# GSM-LCD-ATmega32.net
KiCad netlist of a schematic drawn in Altium Designer
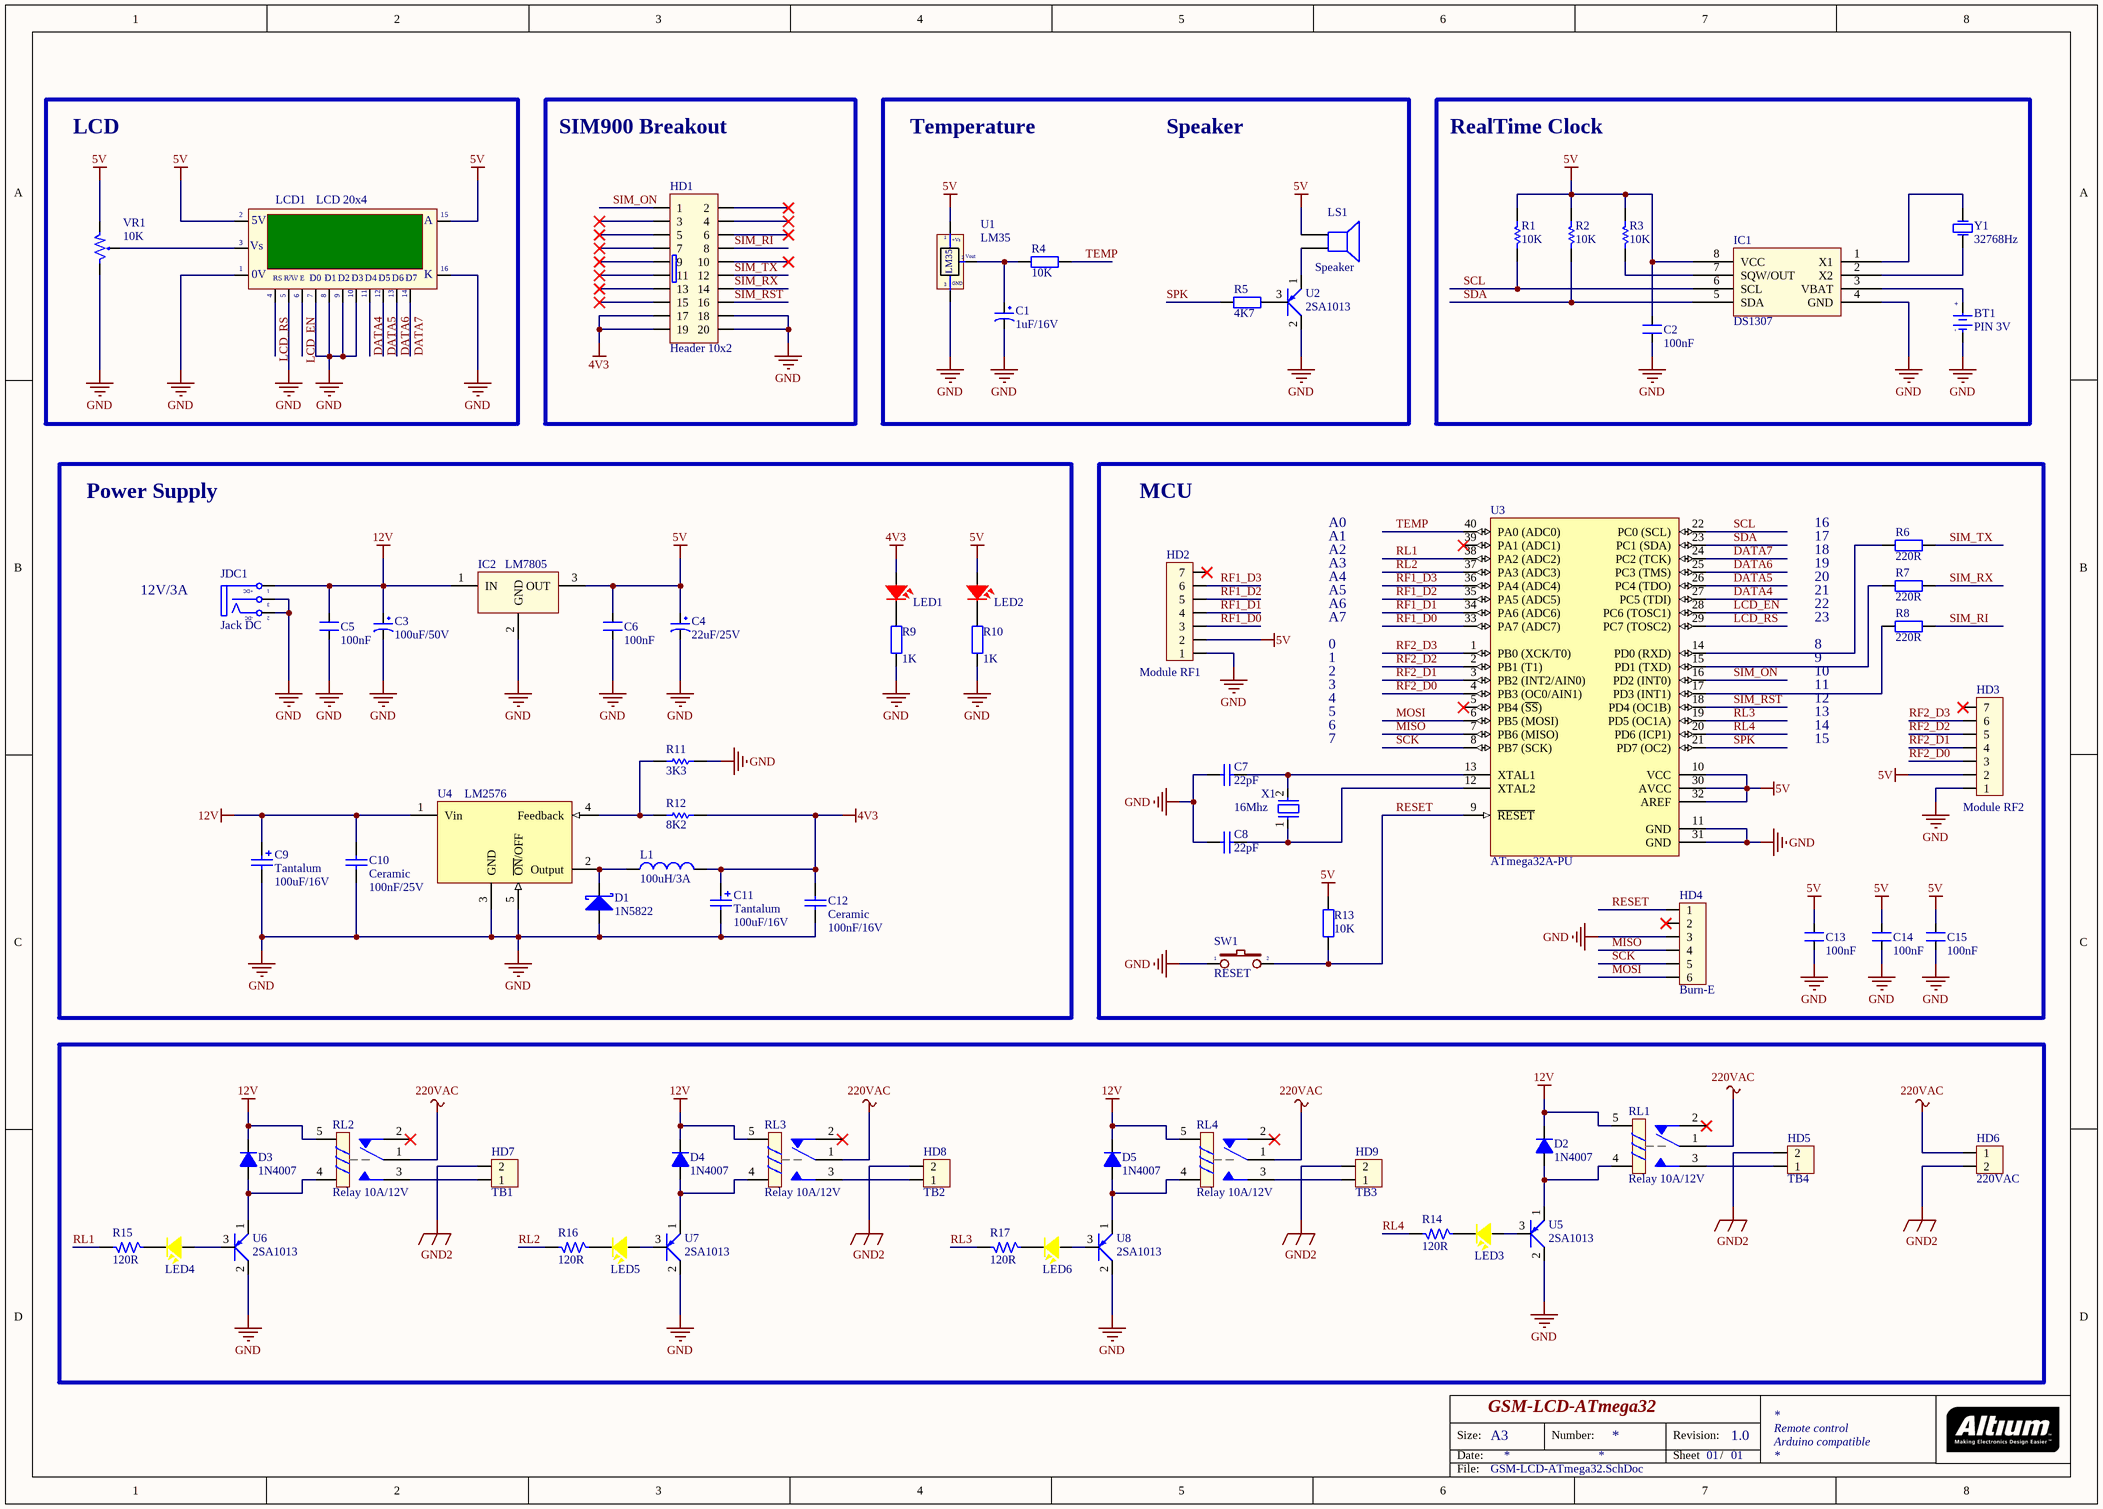
[diagram p0: GSM-LCD-ATmega32.SchDoc]

(export (version "E")
  (design (tool "Eeschema 10.0.6"))
  (components
    (comp (ref "BT1")
      (value "PIN 3V")
      (footprint "PIN3V")
      (description "Battery 3VDC")
      (libsource (lib "lpson") (part "PIN 3V"))
    )
    (comp (ref "C1")
      (value "1uF/16V")
      (footprint "CAP_1UF_50V")
      (description "Cap 100uF/35V - 470uF/16V")
      (libsource (lib "VNELEK") (part "CP3"))
    )
    (comp (ref "C2")
      (value "100nF")
      (footprint "Tu gom 104")
      (description "Cap np 104 => 105pF")
      (libsource (lib "VNELEK") (part "CN2"))
    )
    (comp (ref "C3")
      (value "100uF/50V")
      (footprint "CAP_100UF_50V")
      (description "Cap 100uF/35V - 470uF/16V")
      (libsource (lib "VNELEK") (part "CP3"))
    )
    (comp (ref "C4")
      (value "22uF/25V")
      (footprint "CAP_22UF_50V")
      (description "Cap 100uF/35V - 470uF/16V")
      (libsource (lib "VNELEK") (part "CP3"))
    )
    (comp (ref "C5")
      (value "100nF")
      (footprint "Tu gom 104")
      (description "Cap np 104 => 105pF")
      (libsource (lib "VNELEK") (part "CN2"))
    )
    (comp (ref "C6")
      (value "100nF")
      (footprint "Tu gom 104")
      (description "Cap np 104 => 105pF")
      (libsource (lib "VNELEK") (part "CN2"))
    )
    (comp (ref "C7")
      (value "22pF")
      (footprint "Tu 33p")
      (description "CAP NPO CAPNTO 1nF 100V 10%")
      (fields (field (name "Comment") "5AK102KABAA"))
      (libsource (lib "lpson") (part "5AK102KABAA"))
    )
    (comp (ref "C8")
      (value "22pF")
      (footprint "Tu 33p")
      (description "CAP NPO CAPNTO 1nF 100V 10%")
      (fields (field (name "Comment") "5AK102KABAA"))
      (libsource (lib "lpson") (part "5AK102KABAA"))
    )
    (comp (ref "C9")
      (value "Tantalum")
      (footprint "CAP_100UF_16V")
      (description "Tantalum Capacitor")
      (fields (field (name "ALTIUM_VALUE") "100uF/16V"))
      (libsource (lib "PassiveComponents_Sau") (part "Cap Pol2"))
    )
    (comp (ref "C10")
      (value "Ceramic")
      (footprint "Tu gom 104")
      (description "CeramicCapacitor, 16V, 2.54mm")
      (fields (field (name "ALTIUM_VALUE") "100nF/25V"))
      (libsource (lib "PassiveComponents_Sau") (part "Cap Cera"))
    )
    (comp (ref "C11")
      (value "Tantalum")
      (footprint "CAP_100UF_16V")
      (description "Tantalum Capacitor")
      (fields (field (name "ALTIUM_VALUE") "100uF/16V"))
      (libsource (lib "PassiveComponents_Sau") (part "Cap Pol2"))
    )
    (comp (ref "C12")
      (value "Ceramic")
      (footprint "Tu gom 104")
      (description "CeramicCapacitor, 16V, 2.54mm")
      (fields (field (name "ALTIUM_VALUE") "100nF/16V"))
      (libsource (lib "PassiveComponents_Sau") (part "Cap Cera"))
    )
    (comp (ref "C13")
      (value "100nF")
      (footprint "Tu gom 104")
      (description "Cap np 104 => 105pF")
      (libsource (lib "VNELEK") (part "CN2"))
    )
    (comp (ref "C14")
      (value "100nF")
      (footprint "Tu gom 104")
      (description "Cap np 104 => 105pF")
      (libsource (lib "VNELEK") (part "CN2"))
    )
    (comp (ref "C15")
      (value "100nF")
      (footprint "Tu gom 104")
      (description "Cap np 104 => 105pF")
      (libsource (lib "VNELEK") (part "CN2"))
    )
    (comp (ref "D1")
      (value "1N5822")
      (footprint "1N5822")
      (description "Schottky Rectifier, 40V-3A")
      (fields (field (name "PUBLISHER") "Altium Limited"))
      (libsource (lib "Diodes_Sau") (part "1N5822"))
    )
    (comp (ref "D2")
      (value "1N4007")
      (footprint "1N4007")
      (description "Diode 1A")
      (libsource (lib "VNELEK") (part "D1A"))
    )
    (comp (ref "D3")
      (value "1N4007")
      (footprint "1N4007")
      (description "Diode 1A")
      (libsource (lib "VNELEK") (part "D1A"))
    )
    (comp (ref "D4")
      (value "1N4007")
      (footprint "1N4007")
      (description "Diode 1A")
      (libsource (lib "VNELEK") (part "D1A"))
    )
    (comp (ref "D5")
      (value "1N4007")
      (footprint "1N4007")
      (description "Diode 1A")
      (libsource (lib "VNELEK") (part "D1A"))
    )
    (comp (ref "HD1")
      (value "Header 10x2")
      (footprint "Female Header_10x2")
      (libsource (lib "Tran Tuan") (part "HED10X2"))
    )
    (comp (ref "HD2")
      (value "Module RF1")
      (footprint "FM-Header 7")
      (description "Header 7")
      (libsource (lib "") (part "Hed7_1"))
    )
    (comp (ref "HD3")
      (value "Module RF2")
      (footprint "FM-Header 7")
      (description "Header 7")
      (libsource (lib "Tran Tuan") (part "Hed7"))
    )
    (comp (ref "HD4")
      (value "Burn-E")
      (footprint "CON6")
      (description "Header 6 (Trang)")
      (libsource (lib "Tran Tuan") (part "Hed6"))
    )
    (comp (ref "HD5")
      (value "TB4")
      (footprint "DOMINO 2_pitch 8.5mm")
      (description "Domino 2")
      (libsource (lib "VNELEK") (part "Hed2"))
    )
    (comp (ref "HD6")
      (value "220VAC")
      (footprint "DOMINO 2_pitch 8.5mm")
      (description "Domino 2")
      (libsource (lib "") (part "Hed2_1"))
    )
    (comp (ref "HD7")
      (value "TB1")
      (footprint "DOMINO 2_pitch 8.5mm")
      (description "Domino 2")
      (libsource (lib "VNELEK") (part "Hed2"))
    )
    (comp (ref "HD8")
      (value "TB2")
      (footprint "DOMINO 2_pitch 8.5mm")
      (description "Domino 2")
      (libsource (lib "VNELEK") (part "Hed2"))
    )
    (comp (ref "HD9")
      (value "TB3")
      (footprint "DOMINO 2_pitch 8.5mm")
      (description "Domino 2")
      (libsource (lib "VNELEK") (part "Hed2"))
    )
    (comp (ref "IC1")
      (value "DS1307")
      (footprint "DS1307")
      (description "Serial, I2C Real-Time Clock")
      (libsource (lib "Tran Tuan") (part "DS1307"))
    )
    (comp (ref "IC2")
      (value "LM7805")
      (footprint "LM7805_TN_S")
      (description "On ap +, from + 5 to + 24VDC")
      (libsource (lib "VNELEK") (part "LM78xx"))
    )
    (comp (ref "JDC1")
      (value "Jack DC")
      (footprint "JACK DC-IN")
      (description "Jac DC input")
      (libsource (lib "VNELEK") (part "DCIN"))
    )
    (comp (ref "L1")
      (value "100uH/3A")
      (footprint "Inductor 150mH")
      (description "Inductor")
      (fields (field (name "Comment") "LD26W8-151N") (field (name "PUBLISHER") "Altium Limited"))
      (libsource (lib "PassiveComponents_Sau") (part "Inductor"))
    )
    (comp (ref "LCD1")
      (value "LCD 20x4")
      (footprint "LCD20x4")
      (description "LCD dipslay 20 char, 4 line")
      (libsource (lib "VNELEK") (part "LCD16x2A"))
    )
    (comp (ref "LED1")
      (value "LED-RED")
      (footprint "LED3R")
      (description "LED Single")
      (libsource (lib "Tran Tuan") (part "LED-RED"))
    )
    (comp (ref "LED2")
      (value "LED-RED")
      (footprint "LED3R")
      (description "LED Single")
      (libsource (lib "Tran Tuan") (part "LED-RED"))
    )
    (comp (ref "LED3")
      (value "LED-YELLOW")
      (footprint "LED3Y")
      (description "LED Single")
      (libsource (lib "Tran Tuan") (part "LED-YELLOW"))
    )
    (comp (ref "LED4")
      (value "LED-YELLOW")
      (footprint "LED3Y")
      (description "LED Single")
      (libsource (lib "Tran Tuan") (part "LED-YELLOW"))
    )
    (comp (ref "LED5")
      (value "LED-YELLOW")
      (footprint "LED3Y")
      (description "LED Single")
      (libsource (lib "Tran Tuan") (part "LED-YELLOW"))
    )
    (comp (ref "LED6")
      (value "LED-YELLOW")
      (footprint "LED3Y")
      (description "LED Single")
      (libsource (lib "Tran Tuan") (part "LED-YELLOW"))
    )
    (comp (ref "LS1")
      (value "Speaker")
      (footprint "SPEAKER")
      (description "Loudspeaker")
      (fields (field (name "PUBLISHER") "Altium Limited"))
      (libsource (lib "Miscellaneous Devices") (part "Speaker"))
    )
    (comp (ref "R1")
      (value "10K")
      (footprint "RES 1/4W CFR25")
      (libsource (lib "lpson") (part "CF1/4W1KJ25"))
    )
    (comp (ref "R2")
      (value "10K")
      (footprint "RES 1/4W CFR25")
      (libsource (lib "lpson") (part "CF1/4W1KJ25"))
    )
    (comp (ref "R3")
      (value "10K")
      (footprint "RES 1/4W CFR25")
      (libsource (lib "lpson") (part "CF1/4W1KJ25"))
    )
    (comp (ref "R4")
      (value "10K")
      (footprint "RES 1/4W CFR25")
      (description "Resistor")
      (fields (field (name "Comment") "Res2") (field (name "PUBLISHER") "Altium Limited"))
      (libsource (lib "Miscellaneous Devices") (part "Res2"))
    )
    (comp (ref "R5")
      (value "4K7")
      (footprint "RES 1/4W CFR25")
      (description "Resistor")
      (fields (field (name "Comment") "Res2") (field (name "PUBLISHER") "Altium Limited"))
      (libsource (lib "Miscellaneous Devices") (part "Res2"))
    )
    (comp (ref "R6")
      (value "220R")
      (footprint "RES 1/4W CFR25")
      (description "Resistor")
      (fields (field (name "Comment") "Res2") (field (name "PUBLISHER") "Altium Limited"))
      (libsource (lib "Miscellaneous Devices") (part "Res2"))
    )
    (comp (ref "R7")
      (value "220R")
      (footprint "RES 1/4W CFR25")
      (description "Resistor")
      (fields (field (name "Comment") "Res2") (field (name "PUBLISHER") "Altium Limited"))
      (libsource (lib "Miscellaneous Devices") (part "Res2"))
    )
    (comp (ref "R8")
      (value "220R")
      (footprint "RES 1/4W CFR25")
      (description "Resistor")
      (fields (field (name "Comment") "Res2") (field (name "PUBLISHER") "Altium Limited"))
      (libsource (lib "Miscellaneous Devices") (part "Res2"))
    )
    (comp (ref "R9")
      (value "1K")
      (footprint "RES 1/4W CFR25")
      (description "Resistor")
      (fields (field (name "Comment") "Res2") (field (name "PUBLISHER") "Altium Limited"))
      (libsource (lib "") (part "Res2_1"))
    )
    (comp (ref "R10")
      (value "1K")
      (footprint "RES 1/4W CFR25")
      (description "Resistor")
      (fields (field (name "Comment") "Res2") (field (name "PUBLISHER") "Altium Limited"))
      (libsource (lib "") (part "Res2_1"))
    )
    (comp (ref "R11")
      (value "3K3")
      (footprint "RES 1/4W CFR25")
      (description "Resistor 1/4W, AXIAL-0.3")
      (fields (field (name "Comment") "CFR25S"))
      (libsource (lib "Resistors_Sau") (part "Res1"))
    )
    (comp (ref "R12")
      (value "8K2")
      (footprint "RES 1/4W CFR25")
      (description "Resistor 1/4W, AXIAL-0.3")
      (fields (field (name "Comment") "CFR25S"))
      (libsource (lib "Resistors_Sau") (part "Res1"))
    )
    (comp (ref "R13")
      (value "10K")
      (footprint "RES 1/4W CFR25")
      (description "Resistor")
      (fields (field (name "Comment") "Res2") (field (name "PUBLISHER") "Altium Limited"))
      (libsource (lib "") (part "Res2_1"))
    )
    (comp (ref "R14")
      (value "120R")
      (footprint "RES 1/4W CFR25")
      (description "Resistor 1/4W")
      (libsource (lib "VNELEK") (part "R"))
    )
    (comp (ref "R15")
      (value "120R")
      (footprint "RES 1/4W CFR25")
      (description "Resistor 1/4W")
      (libsource (lib "VNELEK") (part "R"))
    )
    (comp (ref "R16")
      (value "120R")
      (footprint "RES 1/4W CFR25")
      (description "Resistor 1/4W")
      (libsource (lib "VNELEK") (part "R"))
    )
    (comp (ref "R17")
      (value "120R")
      (footprint "RES 1/4W CFR25")
      (description "Resistor 1/4W")
      (libsource (lib "VNELEK") (part "R"))
    )
    (comp (ref "RL1")
      (value "Relay 10A/12V")
      (footprint "RL_10A_12V")
      (description "Relay SPDT,10A - 12VDC 5 Pin")
      (libsource (lib "VNELEK") (part "Relay 1"))
    )
    (comp (ref "RL2")
      (value "Relay 10A/12V")
      (footprint "RL_10A_12V")
      (description "Relay SPDT,10A - 12VDC 5 Pin")
      (libsource (lib "VNELEK") (part "Relay 1"))
    )
    (comp (ref "RL3")
      (value "Relay 10A/12V")
      (footprint "RL_10A_12V")
      (description "Relay SPDT,10A - 12VDC 5 Pin")
      (libsource (lib "VNELEK") (part "Relay 1"))
    )
    (comp (ref "RL4")
      (value "Relay 10A/12V")
      (footprint "RL_10A_12V")
      (description "Relay SPDT,10A - 12VDC 5 Pin")
      (libsource (lib "VNELEK") (part "Relay 1"))
    )
    (comp (ref "SW1")
      (value "RESET")
      (footprint "BUTTON 2PIN TRON")
      (description "Switch button 2 pin")
      (libsource (lib "VNELEK") (part "SW2"))
    )
    (comp (ref "U1")
      (value "LM35")
      (footprint "LM35")
      (description "Teminal")
      (libsource (lib "VNELEK") (part "LM35"))
    )
    (comp (ref "U2")
      (value "2SA1013")
      (footprint "2SA1013")
      (description "PNP Epitaxial Silicon Transistor")
      (libsource (lib "Tran Tuan") (part "2SA1013"))
    )
    (comp (ref "U3")
      (value "ATmega32A-PU")
      (footprint "ATmega32A")
      (fields (field (name "PUBLISHER") "Altium Limited"))
      (libsource (lib "Atmel Microcontroller 8-Bit megaAVR") (part "ATmega32A-PU"))
    )
    (comp (ref "U4")
      (value "LM2576")
      (footprint "LM2576_DIP")
      (description "3.0 A, 15 V, Step-Down  Switching Regulator")
      (libsource (lib "AnalogICs_Sau") (part "LM2576"))
    )
    (comp (ref "U5")
      (value "2SA1013")
      (footprint "2SA1013")
      (description "PNP Epitaxial Silicon Transistor")
      (libsource (lib "Tran Tuan") (part "2SA1013"))
    )
    (comp (ref "U6")
      (value "2SA1013")
      (footprint "2SA1013")
      (description "PNP Epitaxial Silicon Transistor")
      (libsource (lib "Tran Tuan") (part "2SA1013"))
    )
    (comp (ref "U7")
      (value "2SA1013")
      (footprint "2SA1013")
      (description "PNP Epitaxial Silicon Transistor")
      (libsource (lib "Tran Tuan") (part "2SA1013"))
    )
    (comp (ref "U8")
      (value "2SA1013")
      (footprint "2SA1013")
      (description "PNP Epitaxial Silicon Transistor")
      (libsource (lib "Tran Tuan") (part "2SA1013"))
    )
    (comp (ref "VR1")
      (value "10K")
      (footprint "VR1")
      (description "Var Resistor")
      (libsource (lib "VNELEK") (part "VR1"))
    )
    (comp (ref "X1")
      (value "16Mhz")
      (footprint "CRYSTAL 16Mhz")
      (description "Crystal For all Crystal 2pin.")
      (libsource (lib "lpson") (part "XT2"))
    )
    (comp (ref "Y1")
      (value "32768Hz")
      (footprint "Crystal 32.768 Khz_stand")
      (description "Crystal Oscillator 30ppm 20.000MHz")
      (fields (field (name "Comment") "HC49S-20-C-30-30-F-20.000MHz"))
      (libsource (lib "lpson") (part "HC49S-20-C-30-30-F-20.000MHz"))
    )
  )
  (nets
    (net (code "1") (name "/DATA4") (class "Default")
      (node (ref "LCD1") (pin "11") (pinfunction "D4_11") (pintype "passive"))
      (node (ref "U3") (pin "27") (pinfunction "PC5_(TDI)_27") (pintype "bidirectional"))
    )
    (net (code "2") (name "/DATA5") (class "Default")
      (node (ref "LCD1") (pin "12") (pinfunction "D5_12") (pintype "passive"))
      (node (ref "U3") (pin "26") (pinfunction "PC4_(TDO)_26") (pintype "bidirectional"))
    )
    (net (code "3") (name "/DATA6") (class "Default")
      (node (ref "LCD1") (pin "13") (pinfunction "D6_13") (pintype "passive"))
      (node (ref "U3") (pin "25") (pinfunction "PC3_(TMS)_25") (pintype "bidirectional"))
    )
    (net (code "4") (name "/DATA7") (class "Default")
      (node (ref "LCD1") (pin "14") (pinfunction "D7_14") (pintype "passive"))
      (node (ref "U3") (pin "24") (pinfunction "PC2_(TCK)_24") (pintype "bidirectional"))
    )
    (net (code "5") (name "/LCD_EN") (class "Default")
      (node (ref "LCD1") (pin "6") (pinfunction "~{EN}_6") (pintype "passive"))
      (node (ref "U3") (pin "28") (pinfunction "PC6_(TOSC1)_28") (pintype "bidirectional"))
    )
    (net (code "6") (name "/LCD_RS") (class "Default")
      (node (ref "LCD1") (pin "4") (pinfunction "RS_4") (pintype "passive"))
      (node (ref "U3") (pin "29") (pinfunction "PC7_(TOSC2)_29") (pintype "bidirectional"))
    )
    (net (code "7") (name "/MISO") (class "Default")
      (node (ref "HD4") (pin "4") (pinfunction "4_4") (pintype "passive"))
      (node (ref "U3") (pin "7") (pinfunction "PB6_(MISO)_7") (pintype "bidirectional"))
    )
    (net (code "8") (name "/MOSI") (class "Default")
      (node (ref "HD4") (pin "6") (pinfunction "6_6") (pintype "passive"))
      (node (ref "U3") (pin "6") (pinfunction "PB5_(MOSI)_6") (pintype "bidirectional"))
    )
    (net (code "9") (name "/RESET") (class "Default")
      (node (ref "HD4") (pin "1") (pinfunction "1_1") (pintype "passive"))
      (node (ref "R13") (pin "1") (pinfunction "1_1") (pintype "passive"))
      (node (ref "SW1") (pin "2") (pinfunction "2_2") (pintype "passive"))
      (node (ref "U3") (pin "9") (pinfunction "~{RESET}_9") (pintype "input"))
    )
    (net (code "10") (name "/RF1_D0") (class "Default")
      (node (ref "HD2") (pin "3") (pinfunction "3_3") (pintype "passive"))
      (node (ref "U3") (pin "33") (pinfunction "PA7_(ADC7)_33") (pintype "bidirectional"))
    )
    (net (code "11") (name "/RF1_D1") (class "Default")
      (node (ref "HD2") (pin "4") (pinfunction "4_4") (pintype "passive"))
      (node (ref "U3") (pin "34") (pinfunction "PA6_(ADC6)_34") (pintype "bidirectional"))
    )
    (net (code "12") (name "/RF1_D2") (class "Default")
      (node (ref "HD2") (pin "5") (pinfunction "5_5") (pintype "passive"))
      (node (ref "U3") (pin "35") (pinfunction "PA5_(ADC5)_35") (pintype "bidirectional"))
    )
    (net (code "13") (name "/RF1_D3") (class "Default")
      (node (ref "HD2") (pin "6") (pinfunction "6_6") (pintype "passive"))
      (node (ref "U3") (pin "36") (pinfunction "PA4_(ADC4)_36") (pintype "bidirectional"))
    )
    (net (code "14") (name "/RF2_D0") (class "Default")
      (node (ref "HD3") (pin "3") (pinfunction "3_3") (pintype "passive"))
      (node (ref "U3") (pin "4") (pinfunction "PB3_(OC0/AIN1)_4") (pintype "bidirectional"))
    )
    (net (code "15") (name "/RF2_D1") (class "Default")
      (node (ref "HD3") (pin "4") (pinfunction "4_4") (pintype "passive"))
      (node (ref "U3") (pin "3") (pinfunction "PB2_(INT2/AIN0)_3") (pintype "bidirectional"))
    )
    (net (code "16") (name "/RF2_D2") (class "Default")
      (node (ref "HD3") (pin "5") (pinfunction "5_5") (pintype "passive"))
      (node (ref "U3") (pin "2") (pinfunction "PB1_(T1)_2") (pintype "bidirectional"))
    )
    (net (code "17") (name "/RF2_D3") (class "Default")
      (node (ref "HD3") (pin "6") (pinfunction "6_6") (pintype "passive"))
      (node (ref "U3") (pin "1") (pinfunction "PB0_(XCK/T0)_1") (pintype "bidirectional"))
    )
    (net (code "18") (name "/RL1") (class "Default")
      (node (ref "R15") (pin "2") (pinfunction "2_2") (pintype "passive"))
      (node (ref "U3") (pin "38") (pinfunction "PA2_(ADC2)_38") (pintype "bidirectional"))
    )
    (net (code "19") (name "/RL2") (class "Default")
      (node (ref "R16") (pin "2") (pinfunction "2_2") (pintype "passive"))
      (node (ref "U3") (pin "37") (pinfunction "PA3_(ADC3)_37") (pintype "bidirectional"))
    )
    (net (code "20") (name "/RL3") (class "Default")
      (node (ref "R17") (pin "2") (pinfunction "2_2") (pintype "passive"))
      (node (ref "U3") (pin "19") (pinfunction "PD5_(OC1A)_19") (pintype "bidirectional"))
    )
    (net (code "21") (name "/RL4") (class "Default")
      (node (ref "R14") (pin "2") (pinfunction "2_2") (pintype "passive"))
      (node (ref "U3") (pin "20") (pinfunction "PD6_(ICP1)_20") (pintype "bidirectional"))
    )
    (net (code "22") (name "/SCK") (class "Default")
      (node (ref "HD4") (pin "5") (pinfunction "5_5") (pintype "passive"))
      (node (ref "U3") (pin "8") (pinfunction "PB7_(SCK)_8") (pintype "bidirectional"))
    )
    (net (code "23") (name "/SCL") (class "Default")
      (node (ref "IC1") (pin "6") (pinfunction "SCL_6") (pintype "passive"))
      (node (ref "R1") (pin "1") (pinfunction "1_1") (pintype "passive"))
      (node (ref "U3") (pin "22") (pinfunction "PC0_(SCL)_22") (pintype "bidirectional"))
    )
    (net (code "24") (name "/SDA") (class "Default")
      (node (ref "IC1") (pin "5") (pinfunction "SDA_5") (pintype "passive"))
      (node (ref "R2") (pin "1") (pinfunction "1_1") (pintype "passive"))
      (node (ref "U3") (pin "23") (pinfunction "PC1_(SDA)_23") (pintype "bidirectional"))
    )
    (net (code "25") (name "/SIM_ON") (class "Default")
      (node (ref "HD1") (pin "1") (pinfunction "1_1") (pintype "passive"))
      (node (ref "U3") (pin "16") (pinfunction "PD2_(INT0)_16") (pintype "bidirectional"))
    )
    (net (code "26") (name "/SIM_RI") (class "Default")
      (node (ref "HD1") (pin "8") (pinfunction "8_8") (pintype "passive"))
      (node (ref "R8") (pin "2") (pinfunction "2_2") (pintype "passive"))
    )
    (net (code "27") (name "/SIM_RST") (class "Default")
      (node (ref "HD1") (pin "16") (pinfunction "16_16") (pintype "passive"))
      (node (ref "U3") (pin "18") (pinfunction "PD4_(OC1B)_18") (pintype "bidirectional"))
    )
    (net (code "28") (name "/SIM_RX") (class "Default")
      (node (ref "HD1") (pin "14") (pinfunction "14_14") (pintype "passive"))
      (node (ref "R7") (pin "2") (pinfunction "2_2") (pintype "passive"))
    )
    (net (code "29") (name "/SIM_TX") (class "Default")
      (node (ref "HD1") (pin "12") (pinfunction "12_12") (pintype "passive"))
      (node (ref "R6") (pin "2") (pinfunction "2_2") (pintype "passive"))
    )
    (net (code "30") (name "/SPK") (class "Default")
      (node (ref "R5") (pin "1") (pinfunction "1_1") (pintype "passive"))
      (node (ref "U3") (pin "21") (pinfunction "PD7_(OC2)_21") (pintype "bidirectional"))
    )
    (net (code "31") (name "/TEMP") (class "Default")
      (node (ref "R4") (pin "2") (pinfunction "2_2") (pintype "passive"))
      (node (ref "U3") (pin "40") (pinfunction "PA0_(ADC0)_40") (pintype "bidirectional"))
    )
    (net (code "32") (name "4V3") (class "Default")
      (node (ref "C11") (pin "1") (pinfunction "+_1") (pintype "passive"))
      (node (ref "C12") (pin "2") (pinfunction "2_2") (pintype "passive"))
      (node (ref "HD1") (pin "17") (pinfunction "17_17") (pintype "passive"))
      (node (ref "HD1") (pin "19") (pinfunction "19_19") (pintype "passive"))
      (node (ref "L1") (pin "2") (pinfunction "2_2") (pintype "passive"))
      (node (ref "LED1") (pin "1") (pinfunction "1_1") (pintype "passive"))
      (node (ref "R12") (pin "1") (pinfunction "1_1") (pintype "passive"))
    )
    (net (code "33") (name "5V") (class "Default")
      (node (ref "C13") (pin "2") (pinfunction "2_2") (pintype "passive"))
      (node (ref "C14") (pin "2") (pinfunction "2_2") (pintype "passive"))
      (node (ref "C15") (pin "2") (pinfunction "2_2") (pintype "passive"))
      (node (ref "C2") (pin "2") (pinfunction "2_2") (pintype "passive"))
      (node (ref "C4") (pin "1") (pinfunction "1_1") (pintype "passive"))
      (node (ref "C6") (pin "2") (pinfunction "2_2") (pintype "passive"))
      (node (ref "HD2") (pin "2") (pinfunction "2_2") (pintype "passive"))
      (node (ref "HD3") (pin "2") (pinfunction "2_2") (pintype "passive"))
      (node (ref "IC1") (pin "8") (pinfunction "VCC_8") (pintype "passive"))
      (node (ref "IC2") (pin "3") (pinfunction "OUT_3") (pintype "passive"))
      (node (ref "LCD1") (pin "15") (pinfunction "A_15") (pintype "passive"))
      (node (ref "LCD1") (pin "2") (pinfunction "VDD_2") (pintype "passive"))
      (node (ref "LED2") (pin "1") (pinfunction "1_1") (pintype "passive"))
      (node (ref "LS1") (pin "2") (pinfunction "2_2") (pintype "passive"))
      (node (ref "R1") (pin "2") (pinfunction "2_2") (pintype "passive"))
      (node (ref "R13") (pin "2") (pinfunction "2_2") (pintype "passive"))
      (node (ref "R2") (pin "2") (pinfunction "2_2") (pintype "passive"))
      (node (ref "R3") (pin "2") (pinfunction "2_2") (pintype "passive"))
      (node (ref "U1") (pin "1") (pinfunction "+Vs_1") (pintype "passive"))
      (node (ref "U3") (pin "10") (pinfunction "VCC_10") (pintype "power_in"))
      (node (ref "U3") (pin "30") (pinfunction "AVCC_30") (pintype "power_in"))
      (node (ref "U3") (pin "32") (pinfunction "AREF_32") (pintype "power_in"))
      (node (ref "VR1") (pin "1") (pinfunction "1_1") (pintype "passive"))
    )
    (net (code "34") (name "12V") (class "Default")
      (node (ref "C10") (pin "2") (pinfunction "2_2") (pintype "passive"))
      (node (ref "C3") (pin "1") (pinfunction "1_1") (pintype "passive"))
      (node (ref "C5") (pin "2") (pinfunction "2_2") (pintype "passive"))
      (node (ref "C9") (pin "1") (pinfunction "+_1") (pintype "passive"))
      (node (ref "D2") (pin "2") (pinfunction "K_2") (pintype "passive"))
      (node (ref "D3") (pin "2") (pinfunction "K_2") (pintype "passive"))
      (node (ref "D4") (pin "2") (pinfunction "K_2") (pintype "passive"))
      (node (ref "D5") (pin "2") (pinfunction "K_2") (pintype "passive"))
      (node (ref "IC2") (pin "1") (pinfunction "IN_1") (pintype "passive"))
      (node (ref "JDC1") (pin "1") (pinfunction "T_1") (pintype "passive"))
      (node (ref "RL1") (pin "5") (pinfunction "5_5") (pintype "passive"))
      (node (ref "RL2") (pin "5") (pinfunction "5_5") (pintype "passive"))
      (node (ref "RL3") (pin "5") (pinfunction "5_5") (pintype "passive"))
      (node (ref "RL4") (pin "5") (pinfunction "5_5") (pintype "passive"))
      (node (ref "U4") (pin "1") (pinfunction "Vin_1") (pintype "power_in"))
    )
    (net (code "35") (name "220VAC") (class "Default")
      (node (ref "HD6") (pin "1") (pinfunction "1_1") (pintype "passive"))
      (node (ref "RL1") (pin "1") (pinfunction "1_1") (pintype "passive"))
      (node (ref "RL2") (pin "1") (pinfunction "1_1") (pintype "passive"))
      (node (ref "RL3") (pin "1") (pinfunction "1_1") (pintype "passive"))
      (node (ref "RL4") (pin "1") (pinfunction "1_1") (pintype "passive"))
    )
    (net (code "36") (name "GND") (class "Default")
      (node (ref "BT1") (pin "2") (pinfunction "GND_2") (pintype "passive"))
      (node (ref "C1") (pin "2") (pinfunction "2_2") (pintype "passive"))
      (node (ref "C10") (pin "1") (pinfunction "1_1") (pintype "passive"))
      (node (ref "C11") (pin "2") (pinfunction "-_2") (pintype "passive"))
      (node (ref "C12") (pin "1") (pinfunction "1_1") (pintype "passive"))
      (node (ref "C13") (pin "1") (pinfunction "1_1") (pintype "passive"))
      (node (ref "C14") (pin "1") (pinfunction "1_1") (pintype "passive"))
      (node (ref "C15") (pin "1") (pinfunction "1_1") (pintype "passive"))
      (node (ref "C2") (pin "1") (pinfunction "1_1") (pintype "passive"))
      (node (ref "C3") (pin "2") (pinfunction "2_2") (pintype "passive"))
      (node (ref "C4") (pin "2") (pinfunction "2_2") (pintype "passive"))
      (node (ref "C5") (pin "1") (pinfunction "1_1") (pintype "passive"))
      (node (ref "C6") (pin "1") (pinfunction "1_1") (pintype "passive"))
      (node (ref "C7") (pin "1") (pinfunction "1_1") (pintype "passive"))
      (node (ref "C8") (pin "1") (pinfunction "1_1") (pintype "passive"))
      (node (ref "C9") (pin "2") (pinfunction "-_2") (pintype "passive"))
      (node (ref "D1") (pin "1") (pinfunction "A_1") (pintype "passive"))
      (node (ref "HD1") (pin "18") (pinfunction "18_18") (pintype "passive"))
      (node (ref "HD1") (pin "20") (pinfunction "20_20") (pintype "passive"))
      (node (ref "HD2") (pin "1") (pinfunction "1_1") (pintype "passive"))
      (node (ref "HD3") (pin "1") (pinfunction "1_1") (pintype "passive"))
      (node (ref "HD4") (pin "3") (pinfunction "3_3") (pintype "passive"))
      (node (ref "IC1") (pin "4") (pinfunction "GND_4") (pintype "passive"))
      (node (ref "IC2") (pin "2") (pinfunction "GND_2") (pintype "passive"))
      (node (ref "JDC1") (pin "2") (pinfunction "TN_2") (pintype "passive"))
      (node (ref "JDC1") (pin "3") (pinfunction "S_3") (pintype "power_in"))
      (node (ref "LCD1") (pin "1") (pinfunction "GND_1") (pintype "passive"))
      (node (ref "LCD1") (pin "10") (pinfunction "D3_10") (pintype "passive"))
      (node (ref "LCD1") (pin "16") (pinfunction "K_16") (pintype "passive"))
      (node (ref "LCD1") (pin "5") (pinfunction "R/~{W}_5") (pintype "passive"))
      (node (ref "LCD1") (pin "7") (pinfunction "D0_7") (pintype "passive"))
      (node (ref "LCD1") (pin "8") (pinfunction "D1_8") (pintype "passive"))
      (node (ref "LCD1") (pin "9") (pinfunction "D2_9") (pintype "passive"))
      (node (ref "R10") (pin "1") (pinfunction "1_1") (pintype "passive"))
      (node (ref "R11") (pin "2") (pinfunction "2_2") (pintype "passive"))
      (node (ref "R9") (pin "1") (pinfunction "1_1") (pintype "passive"))
      (node (ref "SW1") (pin "1") (pinfunction "1_1") (pintype "passive"))
      (node (ref "U1") (pin "3") (pinfunction "-_3") (pintype "passive"))
      (node (ref "U2") (pin "2") (pinfunction "C_2") (pintype "passive"))
      (node (ref "U3") (pin "11") (pinfunction "GND_11") (pintype "power_in"))
      (node (ref "U3") (pin "31") (pinfunction "GND_31") (pintype "power_in"))
      (node (ref "U4") (pin "3") (pinfunction "GND_3") (pintype "power_in"))
      (node (ref "U4") (pin "5") (pinfunction "~{ON}/OFF_5") (pintype "input"))
      (node (ref "U5") (pin "2") (pinfunction "C_2") (pintype "passive"))
      (node (ref "U6") (pin "2") (pinfunction "C_2") (pintype "passive"))
      (node (ref "U7") (pin "2") (pinfunction "C_2") (pintype "passive"))
      (node (ref "U8") (pin "2") (pinfunction "C_2") (pintype "passive"))
      (node (ref "VR1") (pin "3") (pinfunction "3_3") (pintype "passive"))
    )
    (net (code "37") (name "GND2") (class "Default")
      (node (ref "HD5") (pin "2") (pinfunction "2_2") (pintype "passive"))
      (node (ref "HD6") (pin "2") (pinfunction "2_2") (pintype "passive"))
      (node (ref "HD7") (pin "2") (pinfunction "2_2") (pintype "passive"))
      (node (ref "HD8") (pin "2") (pinfunction "2_2") (pintype "passive"))
      (node (ref "HD9") (pin "2") (pinfunction "2_2") (pintype "passive"))
    )
    (net (code "38") (name "Net-(BT1-+3V)") (class "Default")
      (node (ref "BT1") (pin "1") (pinfunction "+3V_1") (pintype "passive"))
      (node (ref "IC1") (pin "3") (pinfunction "VBAT_3") (pintype "passive"))
    )
    (net (code "39") (name "Net-(D1-K)") (class "Default")
      (node (ref "D1") (pin "2") (pinfunction "K_2") (pintype "passive"))
      (node (ref "L1") (pin "1") (pinfunction "1_1") (pintype "passive"))
      (node (ref "U4") (pin "2") (pinfunction "Output_2") (pintype "power_in"))
    )
    (net (code "40") (name "Net-(D2-A)") (class "Default")
      (node (ref "D2") (pin "1") (pinfunction "A_1") (pintype "passive"))
      (node (ref "RL1") (pin "4") (pinfunction "4_4") (pintype "passive"))
      (node (ref "U5") (pin "1") (pinfunction "E_1") (pintype "passive"))
    )
    (net (code "41") (name "Net-(D3-A)") (class "Default")
      (node (ref "D3") (pin "1") (pinfunction "A_1") (pintype "passive"))
      (node (ref "RL2") (pin "4") (pinfunction "4_4") (pintype "passive"))
      (node (ref "U6") (pin "1") (pinfunction "E_1") (pintype "passive"))
    )
    (net (code "42") (name "Net-(D4-A)") (class "Default")
      (node (ref "D4") (pin "1") (pinfunction "A_1") (pintype "passive"))
      (node (ref "RL3") (pin "4") (pinfunction "4_4") (pintype "passive"))
      (node (ref "U7") (pin "1") (pinfunction "E_1") (pintype "passive"))
    )
    (net (code "43") (name "Net-(D5-A)") (class "Default")
      (node (ref "D5") (pin "1") (pinfunction "A_1") (pintype "passive"))
      (node (ref "RL4") (pin "4") (pinfunction "4_4") (pintype "passive"))
      (node (ref "U8") (pin "1") (pinfunction "E_1") (pintype "passive"))
    )
    (net (code "44") (name "Net-(HD5-Pad1)") (class "Default")
      (node (ref "HD5") (pin "1") (pinfunction "1_1") (pintype "passive"))
      (node (ref "RL1") (pin "3") (pinfunction "3_3") (pintype "passive"))
    )
    (net (code "45") (name "Net-(HD7-Pad1)") (class "Default")
      (node (ref "HD7") (pin "1") (pinfunction "1_1") (pintype "passive"))
      (node (ref "RL2") (pin "3") (pinfunction "3_3") (pintype "passive"))
    )
    (net (code "46") (name "Net-(HD8-Pad1)") (class "Default")
      (node (ref "HD8") (pin "1") (pinfunction "1_1") (pintype "passive"))
      (node (ref "RL3") (pin "3") (pinfunction "3_3") (pintype "passive"))
    )
    (net (code "47") (name "Net-(HD9-Pad1)") (class "Default")
      (node (ref "HD9") (pin "1") (pinfunction "1_1") (pintype "passive"))
      (node (ref "RL4") (pin "3") (pinfunction "3_3") (pintype "passive"))
    )
    (net (code "48") (name "Net-(IC1-SQW{slash}OUT)") (class "Default")
      (node (ref "IC1") (pin "7") (pinfunction "SQW/OUT_7") (pintype "passive"))
      (node (ref "R3") (pin "1") (pinfunction "1_1") (pintype "passive"))
    )
    (net (code "49") (name "Net-(IC1-X1)") (class "Default")
      (node (ref "IC1") (pin "1") (pinfunction "X1_1") (pintype "passive"))
      (node (ref "Y1") (pin "2") (pinfunction "OSC2_2") (pintype "passive"))
    )
    (net (code "50") (name "Net-(IC1-X2)") (class "Default")
      (node (ref "IC1") (pin "2") (pinfunction "X2_2") (pintype "passive"))
      (node (ref "Y1") (pin "1") (pinfunction "OSC1_1") (pintype "passive"))
    )
    (net (code "51") (name "Net-(LCD1-VEE)") (class "Default")
      (node (ref "LCD1") (pin "3") (pinfunction "VEE_3") (pintype "passive"))
      (node (ref "VR1") (pin "2") (pinfunction "2_2") (pintype "passive"))
    )
    (net (code "52") (name "Net-(LED1-Pad2)") (class "Default")
      (node (ref "LED1") (pin "2") (pinfunction "2_2") (pintype "passive"))
      (node (ref "R9") (pin "2") (pinfunction "2_2") (pintype "passive"))
    )
    (net (code "53") (name "Net-(LED2-Pad2)") (class "Default")
      (node (ref "LED2") (pin "2") (pinfunction "2_2") (pintype "passive"))
      (node (ref "R10") (pin "2") (pinfunction "2_2") (pintype "passive"))
    )
    (net (code "54") (name "Net-(LED3-Pad2)") (class "Default")
      (node (ref "LED3") (pin "2") (pinfunction "2_2") (pintype "passive"))
      (node (ref "R14") (pin "1") (pinfunction "1_1") (pintype "passive"))
    )
    (net (code "55") (name "Net-(LED4-Pad2)") (class "Default")
      (node (ref "LED4") (pin "2") (pinfunction "2_2") (pintype "passive"))
      (node (ref "R15") (pin "1") (pinfunction "1_1") (pintype "passive"))
    )
    (net (code "56") (name "Net-(LED5-Pad2)") (class "Default")
      (node (ref "LED5") (pin "2") (pinfunction "2_2") (pintype "passive"))
      (node (ref "R16") (pin "1") (pinfunction "1_1") (pintype "passive"))
    )
    (net (code "57") (name "Net-(LED6-Pad2)") (class "Default")
      (node (ref "LED6") (pin "2") (pinfunction "2_2") (pintype "passive"))
      (node (ref "R17") (pin "1") (pinfunction "1_1") (pintype "passive"))
    )
    (net (code "58") (name "Net-(U1-Vout)") (class "Default")
      (node (ref "C1") (pin "1") (pinfunction "1_1") (pintype "passive"))
      (node (ref "R4") (pin "1") (pinfunction "1_1") (pintype "passive"))
      (node (ref "U1") (pin "2") (pinfunction "Vout_2") (pintype "passive"))
    )
    (net (code "59") (name "Net-(U2-B)") (class "Default")
      (node (ref "R5") (pin "2") (pinfunction "2_2") (pintype "passive"))
      (node (ref "U2") (pin "3") (pinfunction "B_3") (pintype "passive"))
    )
    (net (code "60") (name "Net-(U2-E)") (class "Default")
      (node (ref "LS1") (pin "1") (pinfunction "1_1") (pintype "passive"))
      (node (ref "U2") (pin "1") (pinfunction "E_1") (pintype "passive"))
    )
    (net (code "61") (name "Net-(U3-PD0_(RXD))") (class "Default")
      (node (ref "R6") (pin "1") (pinfunction "1_1") (pintype "passive"))
      (node (ref "U3") (pin "14") (pinfunction "PD0_(RXD)_14") (pintype "bidirectional"))
    )
    (net (code "62") (name "Net-(U3-PD1_(TXD))") (class "Default")
      (node (ref "R7") (pin "1") (pinfunction "1_1") (pintype "passive"))
      (node (ref "U3") (pin "15") (pinfunction "PD1_(TXD)_15") (pintype "bidirectional"))
    )
    (net (code "63") (name "Net-(U3-PD3_(INT1))") (class "Default")
      (node (ref "R8") (pin "1") (pinfunction "1_1") (pintype "passive"))
      (node (ref "U3") (pin "17") (pinfunction "PD3_(INT1)_17") (pintype "bidirectional"))
    )
    (net (code "64") (name "Net-(U3-XTAL1)") (class "Default")
      (node (ref "C7") (pin "2") (pinfunction "2_2") (pintype "passive"))
      (node (ref "U3") (pin "13") (pinfunction "XTAL1_13") (pintype "passive"))
      (node (ref "X1") (pin "2") (pinfunction "2_2") (pintype "passive"))
    )
    (net (code "65") (name "Net-(U3-XTAL2)") (class "Default")
      (node (ref "C8") (pin "2") (pinfunction "2_2") (pintype "passive"))
      (node (ref "U3") (pin "12") (pinfunction "XTAL2_12") (pintype "passive"))
      (node (ref "X1") (pin "1") (pinfunction "1_1") (pintype "passive"))
    )
    (net (code "66") (name "Net-(U4-Feedback)") (class "Default")
      (node (ref "R11") (pin "1") (pinfunction "1_1") (pintype "passive"))
      (node (ref "R12") (pin "2") (pinfunction "2_2") (pintype "passive"))
      (node (ref "U4") (pin "4") (pinfunction "Feedback_4") (pintype "input"))
    )
    (net (code "67") (name "Net-(U5-B)") (class "Default")
      (node (ref "LED3") (pin "1") (pinfunction "1_1") (pintype "passive"))
      (node (ref "U5") (pin "3") (pinfunction "B_3") (pintype "passive"))
    )
    (net (code "68") (name "Net-(U6-B)") (class "Default")
      (node (ref "LED4") (pin "1") (pinfunction "1_1") (pintype "passive"))
      (node (ref "U6") (pin "3") (pinfunction "B_3") (pintype "passive"))
    )
    (net (code "69") (name "Net-(U7-B)") (class "Default")
      (node (ref "LED5") (pin "1") (pinfunction "1_1") (pintype "passive"))
      (node (ref "U7") (pin "3") (pinfunction "B_3") (pintype "passive"))
    )
    (net (code "70") (name "Net-(U8-B)") (class "Default")
      (node (ref "LED6") (pin "1") (pinfunction "1_1") (pintype "passive"))
      (node (ref "U8") (pin "3") (pinfunction "B_3") (pintype "passive"))
    )
    (net (code "71") (name "unconnected-(HD1-Pad2)") (class "Default")
      (node (ref "HD1") (pin "2") (pinfunction "2_2") (pintype "passive+no_connect"))
    )
    (net (code "72") (name "unconnected-(HD1-Pad3)") (class "Default")
      (node (ref "HD1") (pin "3") (pinfunction "3_3") (pintype "passive+no_connect"))
    )
    (net (code "73") (name "unconnected-(HD1-Pad4)") (class "Default")
      (node (ref "HD1") (pin "4") (pinfunction "4_4") (pintype "passive+no_connect"))
    )
    (net (code "74") (name "unconnected-(HD1-Pad5)") (class "Default")
      (node (ref "HD1") (pin "5") (pinfunction "5_5") (pintype "passive+no_connect"))
    )
    (net (code "75") (name "unconnected-(HD1-Pad6)") (class "Default")
      (node (ref "HD1") (pin "6") (pinfunction "6_6") (pintype "passive+no_connect"))
    )
    (net (code "76") (name "unconnected-(HD1-Pad7)") (class "Default")
      (node (ref "HD1") (pin "7") (pinfunction "7_7") (pintype "passive+no_connect"))
    )
    (net (code "77") (name "unconnected-(HD1-Pad9)") (class "Default")
      (node (ref "HD1") (pin "9") (pinfunction "9_9") (pintype "passive+no_connect"))
    )
    (net (code "78") (name "unconnected-(HD1-Pad10)") (class "Default")
      (node (ref "HD1") (pin "10") (pinfunction "10_10") (pintype "passive+no_connect"))
    )
    (net (code "79") (name "unconnected-(HD1-Pad11)") (class "Default")
      (node (ref "HD1") (pin "11") (pinfunction "11_11") (pintype "passive+no_connect"))
    )
    (net (code "80") (name "unconnected-(HD1-Pad13)") (class "Default")
      (node (ref "HD1") (pin "13") (pinfunction "13_13") (pintype "passive+no_connect"))
    )
    (net (code "81") (name "unconnected-(HD1-Pad15)") (class "Default")
      (node (ref "HD1") (pin "15") (pinfunction "15_15") (pintype "passive+no_connect"))
    )
    (net (code "82") (name "unconnected-(HD2-Pad7)") (class "Default")
      (node (ref "HD2") (pin "7") (pinfunction "7_7") (pintype "passive+no_connect"))
    )
    (net (code "83") (name "unconnected-(HD3-Pad7)") (class "Default")
      (node (ref "HD3") (pin "7") (pinfunction "7_7") (pintype "passive+no_connect"))
    )
    (net (code "84") (name "unconnected-(HD4-Pad2)") (class "Default")
      (node (ref "HD4") (pin "2") (pinfunction "2_2") (pintype "passive+no_connect"))
    )
    (net (code "85") (name "unconnected-(RL1-Pad2)") (class "Default")
      (node (ref "RL1") (pin "2") (pinfunction "2_2") (pintype "passive+no_connect"))
    )
    (net (code "86") (name "unconnected-(RL2-Pad2)") (class "Default")
      (node (ref "RL2") (pin "2") (pinfunction "2_2") (pintype "passive+no_connect"))
    )
    (net (code "87") (name "unconnected-(RL3-Pad2)") (class "Default")
      (node (ref "RL3") (pin "2") (pinfunction "2_2") (pintype "passive+no_connect"))
    )
    (net (code "88") (name "unconnected-(RL4-Pad2)") (class "Default")
      (node (ref "RL4") (pin "2") (pinfunction "2_2") (pintype "passive+no_connect"))
    )
    (net (code "89") (name "unconnected-(U3-PA1_(ADC1)-Pad39)") (class "Default")
      (node (ref "U3") (pin "39") (pinfunction "PA1_(ADC1)_39") (pintype "bidirectional+no_connect"))
    )
    (net (code "90") (name "unconnected-(U3-PB4_(~{SS})-Pad5)") (class "Default")
      (node (ref "U3") (pin "5") (pinfunction "PB4_(~{SS})_5") (pintype "bidirectional+no_connect"))
    )
    (net (code "91") (name "unconnected-(X1-GND-Pad3)") (class "Default")
      (node (ref "X1") (pin "3") (pinfunction "GND_3") (pintype "passive"))
    )
  )
)
